# Power-Connectors.net
KiCad netlist of a schematic drawn in Altium Designer
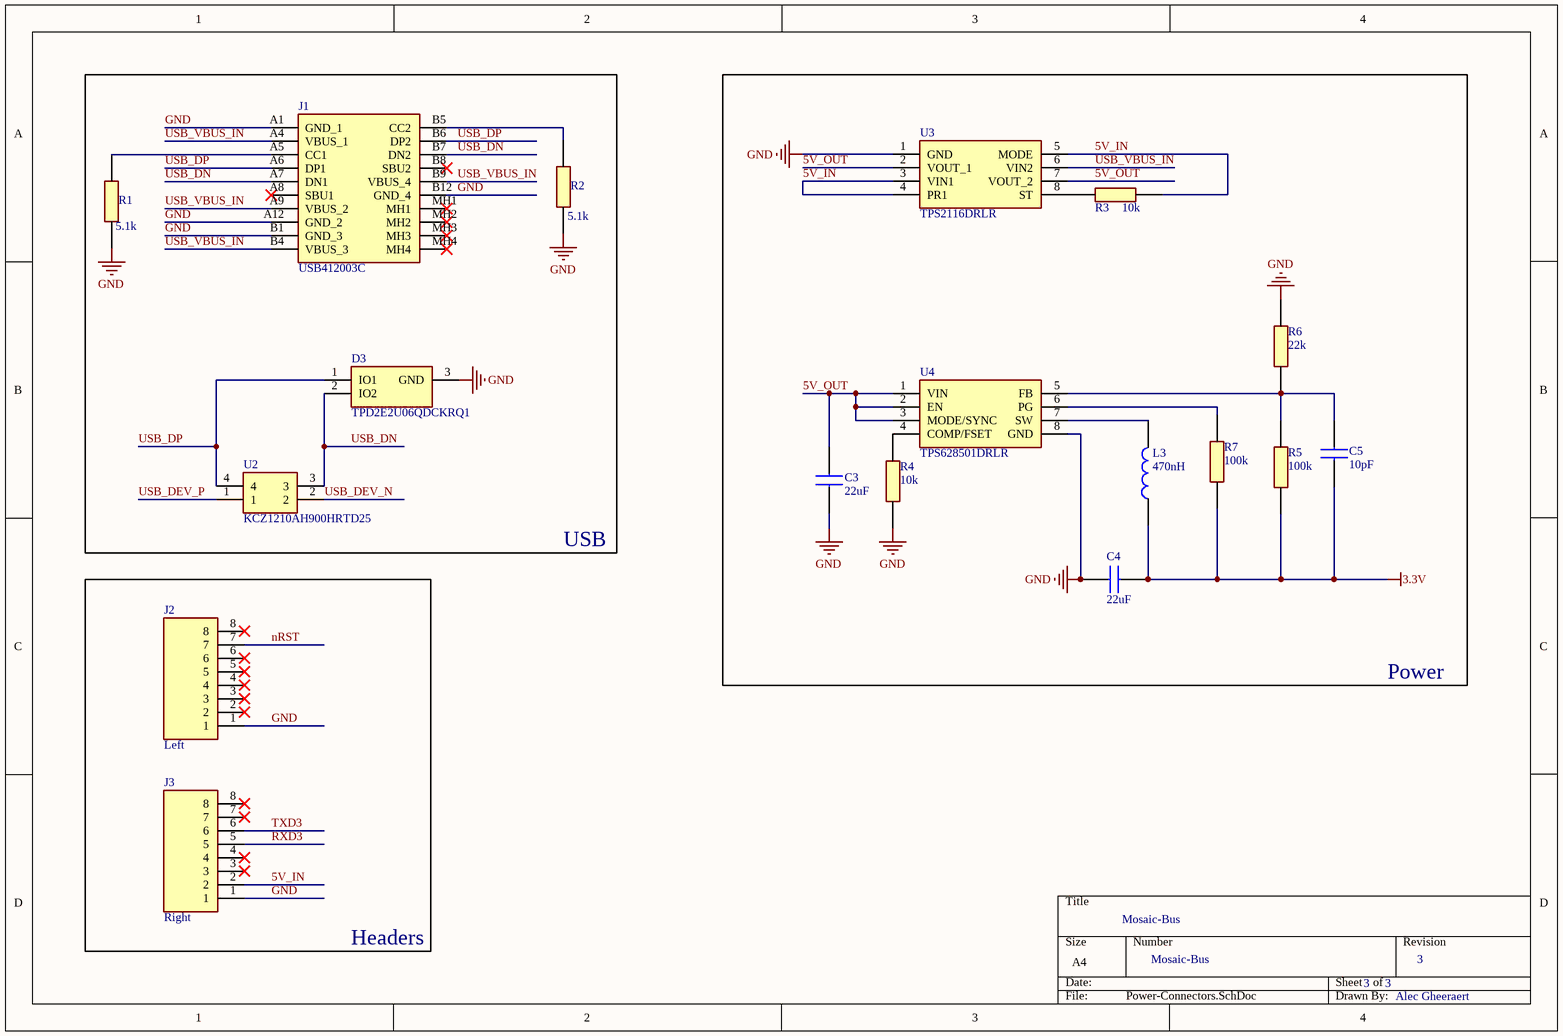
[diagram p0: Power-Connectors.SchDoc]

(export (version "E")
  (design (tool "Eeschema 10.0.6"))
  (components
    (comp (ref "C3")
      (value "22uF")
      (footprint "CAPC3317X190N")
      (description "22uF Capacitor")
      (fields (field (name "MANUFACTURER") "Walsin") (field (name "TOLERANCE") "10%"))
      (libsource (lib "Ghrt") (part "1206X226K160CT"))
    )
    (comp (ref "C4")
      (value "22uF")
      (footprint "CAPC3317X190N")
      (description "22uF Capacitor")
      (fields (field (name "MANUFACTURER") "Walsin") (field (name "TOLERANCE") "10%"))
      (libsource (lib "Ghrt") (part "1206X226K160CT"))
    )
    (comp (ref "C5")
      (value "10pF")
      (footprint "CAPC1608X95N")
      (description "10pF Capacitor")
      (fields (field (name "MANUFACTURER") "Walsin") (field (name "TOLERANCE") "1%"))
      (libsource (lib "Ghrt") (part "0603N100F101CT"))
    )
    (comp (ref "D3")
      (value "TPD2E2U06QDCKRQ1")
      (footprint "TPD2E2U06QDCKRQ1")
      (description "TVS Diode Unidirectional 2-Channel")
      (fields (field (name "MANUFACTURER") "Texas Instruments"))
      (libsource (lib "Ghrt") (part "TPD2E2U06QDCKRQ1"))
    )
    (comp (ref "J1")
      (value "USB412003C")
      (footprint "USB412003C")
      (description "USB-C Connector 16P Vertical")
      (fields (field (name "MANUFACTURER") "Global Connector Technology"))
      (libsource (lib "Ghrt") (part "USB412003C"))
    )
    (comp (ref "J2")
      (value "Left")
      (footprint "HDRV8W63P0X254_1X8_2032X254X970P")
      (description "Headers & Wire Housings 8P SINGLE ROW")
      (libsource (lib "Ghrt") (part "825433-8"))
    )
    (comp (ref "J3")
      (value "Right")
      (footprint "HDRV8W63P0X254_1X8_2032X254X970P")
      (description "Headers & Wire Housings 8P SINGLE ROW")
      (libsource (lib "Ghrt") (part "825433-8"))
    )
    (comp (ref "L3")
      (value "470nH")
      (footprint "INDC2016X100N")
      (description "470nH Inductor")
      (fields (field (name "TOLERANCE") "30%") (field (name "MANUFACTURER") "Wurth Elektronik"))
      (libsource (lib "Ghrt") (part "744383430047"))
    )
    (comp (ref "R1")
      (value "5.1k")
      (footprint "RESC1608X60N")
      (description "5.1kOhm Resistor")
      (fields (field (name "TOLERANCE") "1%") (field (name "MANUFACTURER") "Walsin"))
      (libsource (lib "Ghrt") (part "WR06X5101FTL"))
    )
    (comp (ref "R2")
      (value "5.1k")
      (footprint "RESC1608X60N")
      (description "5.1kOhm Resistor")
      (fields (field (name "TOLERANCE") "1%") (field (name "MANUFACTURER") "Walsin"))
      (libsource (lib "Ghrt") (part "WR06X5101FTL"))
    )
    (comp (ref "R3")
      (value "10k")
      (footprint "RESC1608X60N")
      (description "10kOhm Resistor")
      (fields (field (name "MANUFACTURER") "Walsin") (field (name "TOLERANCE") "5%"))
      (libsource (lib "Ghrt") (part "WR06X103JTR"))
    )
    (comp (ref "R4")
      (value "10k")
      (footprint "RESC1608X60N")
      (description "10kOhm Resistor")
      (fields (field (name "MANUFACTURER") "Walsin") (field (name "TOLERANCE") "5%"))
      (libsource (lib "") (part "WR06X103JTR_1"))
    )
    (comp (ref "R5")
      (value "100k")
      (footprint "RESC1608X60N")
      (description "100kOhm Resistor")
      (fields (field (name "TOLERANCE") "5%") (field (name "MANUFACTURER") "Walsin"))
      (libsource (lib "Ghrt") (part "WR06X104JTL"))
    )
    (comp (ref "R6")
      (value "22k")
      (footprint "RESC1608X60N")
      (description "22kOhm Resistor")
      (fields (field (name "TOLERANCE") "5%") (field (name "MANUFACTURER") "Walsin"))
      (libsource (lib "Ghrt") (part "WR06X223JTL"))
    )
    (comp (ref "R7")
      (value "100k")
      (footprint "RESC1608X60N")
      (description "100kOhm Resistor")
      (fields (field (name "TOLERANCE") "5%") (field (name "MANUFACTURER") "Walsin"))
      (libsource (lib "Ghrt") (part "WR06X104JTL"))
    )
    (comp (ref "U2")
      (value "KCZ1210AH900HRTD25")
      (footprint "KCZ1210AH900HRTD25")
      (description "Common Mode Filters / Chokes,")
      (libsource (lib "Ghrt") (part "KCZ1210AH900HRTD25"))
    )
    (comp (ref "U3")
      (value "TPS2116DRLR")
      (footprint "TPS2116DRLR")
      (description "Power Multiplexer 1 Output 1.6V-5.5V 2.5A")
      (fields (field (name "MANUFACTURER") "Texas Instruments"))
      (libsource (lib "Ghrt") (part "TPS2116DRLR"))
    )
    (comp (ref "U4")
      (value "TPS628501DRLR")
      (footprint "TPS628501DRLR")
      (description "Switching Voltage Regulator Buck 600mV-5.5V 1A")
      (fields (field (name "MANUFACTURER") "Texas Instruments"))
      (libsource (lib "Ghrt") (part "TPS628501DRLR"))
    )
  )
  (nets
    (net (code "1") (name "/5V_IN") (class "Default")
      (node (ref "J3") (pin "2") (pinfunction "2_2") (pintype "passive"))
      (node (ref "R3") (pin "2") (pinfunction "2_2") (pintype "passive"))
      (node (ref "U3") (pin "3") (pinfunction "VIN1_3") (pintype "passive"))
      (node (ref "U3") (pin "4") (pinfunction "PR1_4") (pintype "passive"))
      (node (ref "U3") (pin "5") (pinfunction "MODE_5") (pintype "passive"))
    )
    (net (code "2") (name "/5V_OUT") (class "Default")
      (node (ref "C3") (pin "2") (pinfunction "2_2") (pintype "passive"))
      (node (ref "U3") (pin "2") (pinfunction "VOUT_1_2") (pintype "passive"))
      (node (ref "U3") (pin "7") (pinfunction "VOUT_2_7") (pintype "passive"))
      (node (ref "U4") (pin "1") (pinfunction "VIN_1") (pintype "passive"))
      (node (ref "U4") (pin "2") (pinfunction "EN_2") (pintype "passive"))
      (node (ref "U4") (pin "3") (pinfunction "MODE/SYNC_3") (pintype "passive"))
    )
    (net (code "3") (name "/RXD3") (class "Default")
      (node (ref "J3") (pin "5") (pinfunction "5_5") (pintype "passive"))
    )
    (net (code "4") (name "/TXD3") (class "Default")
      (node (ref "J3") (pin "6") (pinfunction "6_6") (pintype "passive"))
    )
    (net (code "5") (name "/USB_DEV_N") (class "Default")
      (node (ref "U2") (pin "2") (pinfunction "2_2") (pintype "passive"))
    )
    (net (code "6") (name "/USB_DEV_P") (class "Default")
      (node (ref "U2") (pin "1") (pinfunction "1_1") (pintype "passive"))
    )
    (net (code "7") (name "/USB_DN") (class "Default")
      (node (ref "D3") (pin "2") (pinfunction "IO2_2") (pintype "passive"))
      (node (ref "J1") (pin "A7") (pinfunction "DN1_A7") (pintype "passive"))
      (node (ref "J1") (pin "B7") (pinfunction "DN2_B7") (pintype "passive"))
      (node (ref "U2") (pin "3") (pinfunction "3_3") (pintype "passive"))
    )
    (net (code "8") (name "/USB_DP") (class "Default")
      (node (ref "D3") (pin "1") (pinfunction "IO1_1") (pintype "passive"))
      (node (ref "J1") (pin "A6") (pinfunction "DP1_A6") (pintype "passive"))
      (node (ref "J1") (pin "B6") (pinfunction "DP2_B6") (pintype "passive"))
      (node (ref "U2") (pin "4") (pinfunction "4_4") (pintype "passive"))
    )
    (net (code "9") (name "/USB_VBUS_IN") (class "Default")
      (node (ref "J1") (pin "A4") (pinfunction "VBUS_1_A4") (pintype "passive"))
      (node (ref "J1") (pin "A9") (pinfunction "VBUS_2_A9") (pintype "passive"))
      (node (ref "J1") (pin "B4") (pinfunction "VBUS_3_B4") (pintype "passive"))
      (node (ref "J1") (pin "B9") (pinfunction "VBUS_4_B9") (pintype "passive"))
      (node (ref "U3") (pin "6") (pinfunction "VIN2_6") (pintype "passive"))
    )
    (net (code "10") (name "/nRST") (class "Default")
      (node (ref "J2") (pin "7") (pinfunction "7_7") (pintype "passive"))
    )
    (net (code "11") (name "3.3V") (class "Default")
      (node (ref "C4") (pin "1") (pinfunction "1_1") (pintype "passive"))
      (node (ref "C5") (pin "2") (pinfunction "2_2") (pintype "passive"))
      (node (ref "L3") (pin "1") (pinfunction "1_1") (pintype "passive"))
      (node (ref "R5") (pin "2") (pinfunction "2_2") (pintype "passive"))
      (node (ref "R7") (pin "2") (pinfunction "2_2") (pintype "passive"))
    )
    (net (code "12") (name "GND") (class "Default")
      (node (ref "C3") (pin "1") (pinfunction "1_1") (pintype "passive"))
      (node (ref "C4") (pin "2") (pinfunction "2_2") (pintype "passive"))
      (node (ref "D3") (pin "3") (pinfunction "GND_3") (pintype "passive"))
      (node (ref "J1") (pin "A1") (pinfunction "GND_1_A1") (pintype "passive"))
      (node (ref "J1") (pin "A12") (pinfunction "GND_2_A12") (pintype "passive"))
      (node (ref "J1") (pin "B1") (pinfunction "GND_3_B1") (pintype "passive"))
      (node (ref "J1") (pin "B12") (pinfunction "GND_4_B12") (pintype "passive"))
      (node (ref "J2") (pin "1") (pinfunction "1_1") (pintype "passive"))
      (node (ref "J3") (pin "1") (pinfunction "1_1") (pintype "passive"))
      (node (ref "R1") (pin "2") (pinfunction "2_2") (pintype "passive"))
      (node (ref "R2") (pin "2") (pinfunction "2_2") (pintype "passive"))
      (node (ref "R4") (pin "2") (pinfunction "2_2") (pintype "passive"))
      (node (ref "R6") (pin "1") (pinfunction "1_1") (pintype "passive"))
      (node (ref "U3") (pin "1") (pinfunction "GND_1") (pintype "passive"))
      (node (ref "U4") (pin "8") (pinfunction "GND_8") (pintype "passive"))
    )
    (net (code "13") (name "Net-(J1-CC1)") (class "Default")
      (node (ref "J1") (pin "A5") (pinfunction "CC1_A5") (pintype "passive"))
      (node (ref "R1") (pin "1") (pinfunction "1_1") (pintype "passive"))
    )
    (net (code "14") (name "Net-(J1-CC2)") (class "Default")
      (node (ref "J1") (pin "B5") (pinfunction "CC2_B5") (pintype "passive"))
      (node (ref "R2") (pin "1") (pinfunction "1_1") (pintype "passive"))
    )
    (net (code "15") (name "Net-(U3-ST)") (class "Default")
      (node (ref "R3") (pin "1") (pinfunction "1_1") (pintype "passive"))
      (node (ref "U3") (pin "8") (pinfunction "ST_8") (pintype "passive"))
    )
    (net (code "16") (name "Net-(U4-COMP{slash}FSET)") (class "Default")
      (node (ref "R4") (pin "1") (pinfunction "1_1") (pintype "passive"))
      (node (ref "U4") (pin "4") (pinfunction "COMP/FSET_4") (pintype "passive"))
    )
    (net (code "17") (name "Net-(U4-FB)") (class "Default")
      (node (ref "C5") (pin "1") (pinfunction "1_1") (pintype "passive"))
      (node (ref "R5") (pin "1") (pinfunction "1_1") (pintype "passive"))
      (node (ref "R6") (pin "2") (pinfunction "2_2") (pintype "passive"))
      (node (ref "U4") (pin "5") (pinfunction "FB_5") (pintype "passive"))
    )
    (net (code "18") (name "Net-(U4-PG)") (class "Default")
      (node (ref "R7") (pin "1") (pinfunction "1_1") (pintype "passive"))
      (node (ref "U4") (pin "6") (pinfunction "PG_6") (pintype "passive"))
    )
    (net (code "19") (name "Net-(U4-SW)") (class "Default")
      (node (ref "L3") (pin "2") (pinfunction "2_2") (pintype "passive"))
      (node (ref "U4") (pin "7") (pinfunction "SW_7") (pintype "passive"))
    )
    (net (code "20") (name "unconnected-(J1-PadMH1)") (class "Default")
      (node (ref "J1") (pin "MH1") (pinfunction "MH1_MH1") (pintype "passive+no_connect"))
    )
    (net (code "21") (name "unconnected-(J1-PadMH2)") (class "Default")
      (node (ref "J1") (pin "MH2") (pinfunction "MH2_MH2") (pintype "passive+no_connect"))
    )
    (net (code "22") (name "unconnected-(J1-PadMH3)") (class "Default")
      (node (ref "J1") (pin "MH3") (pinfunction "MH3_MH3") (pintype "passive+no_connect"))
    )
    (net (code "23") (name "unconnected-(J1-PadMH4)") (class "Default")
      (node (ref "J1") (pin "MH4") (pinfunction "MH4_MH4") (pintype "passive+no_connect"))
    )
    (net (code "24") (name "unconnected-(J1-SBU1-PadA8)") (class "Default")
      (node (ref "J1") (pin "A8") (pinfunction "SBU1_A8") (pintype "passive+no_connect"))
    )
    (net (code "25") (name "unconnected-(J1-SBU2-PadB8)") (class "Default")
      (node (ref "J1") (pin "B8") (pinfunction "SBU2_B8") (pintype "passive+no_connect"))
    )
    (net (code "26") (name "unconnected-(J2-Pad2)") (class "Default")
      (node (ref "J2") (pin "2") (pinfunction "2_2") (pintype "passive+no_connect"))
    )
    (net (code "27") (name "unconnected-(J2-Pad3)") (class "Default")
      (node (ref "J2") (pin "3") (pinfunction "3_3") (pintype "passive+no_connect"))
    )
    (net (code "28") (name "unconnected-(J2-Pad4)") (class "Default")
      (node (ref "J2") (pin "4") (pinfunction "4_4") (pintype "passive+no_connect"))
    )
    (net (code "29") (name "unconnected-(J2-Pad5)") (class "Default")
      (node (ref "J2") (pin "5") (pinfunction "5_5") (pintype "passive+no_connect"))
    )
    (net (code "30") (name "unconnected-(J2-Pad6)") (class "Default")
      (node (ref "J2") (pin "6") (pinfunction "6_6") (pintype "passive+no_connect"))
    )
    (net (code "31") (name "unconnected-(J2-Pad8)") (class "Default")
      (node (ref "J2") (pin "8") (pinfunction "8_8") (pintype "passive+no_connect"))
    )
    (net (code "32") (name "unconnected-(J3-Pad3)") (class "Default")
      (node (ref "J3") (pin "3") (pinfunction "3_3") (pintype "passive+no_connect"))
    )
    (net (code "33") (name "unconnected-(J3-Pad4)") (class "Default")
      (node (ref "J3") (pin "4") (pinfunction "4_4") (pintype "passive+no_connect"))
    )
    (net (code "34") (name "unconnected-(J3-Pad7)") (class "Default")
      (node (ref "J3") (pin "7") (pinfunction "7_7") (pintype "passive+no_connect"))
    )
    (net (code "35") (name "unconnected-(J3-Pad8)") (class "Default")
      (node (ref "J3") (pin "8") (pinfunction "8_8") (pintype "passive+no_connect"))
    )
  )
)
